# xbowtie2.net
KiCad netlist of a schematic drawn in Altium Designer
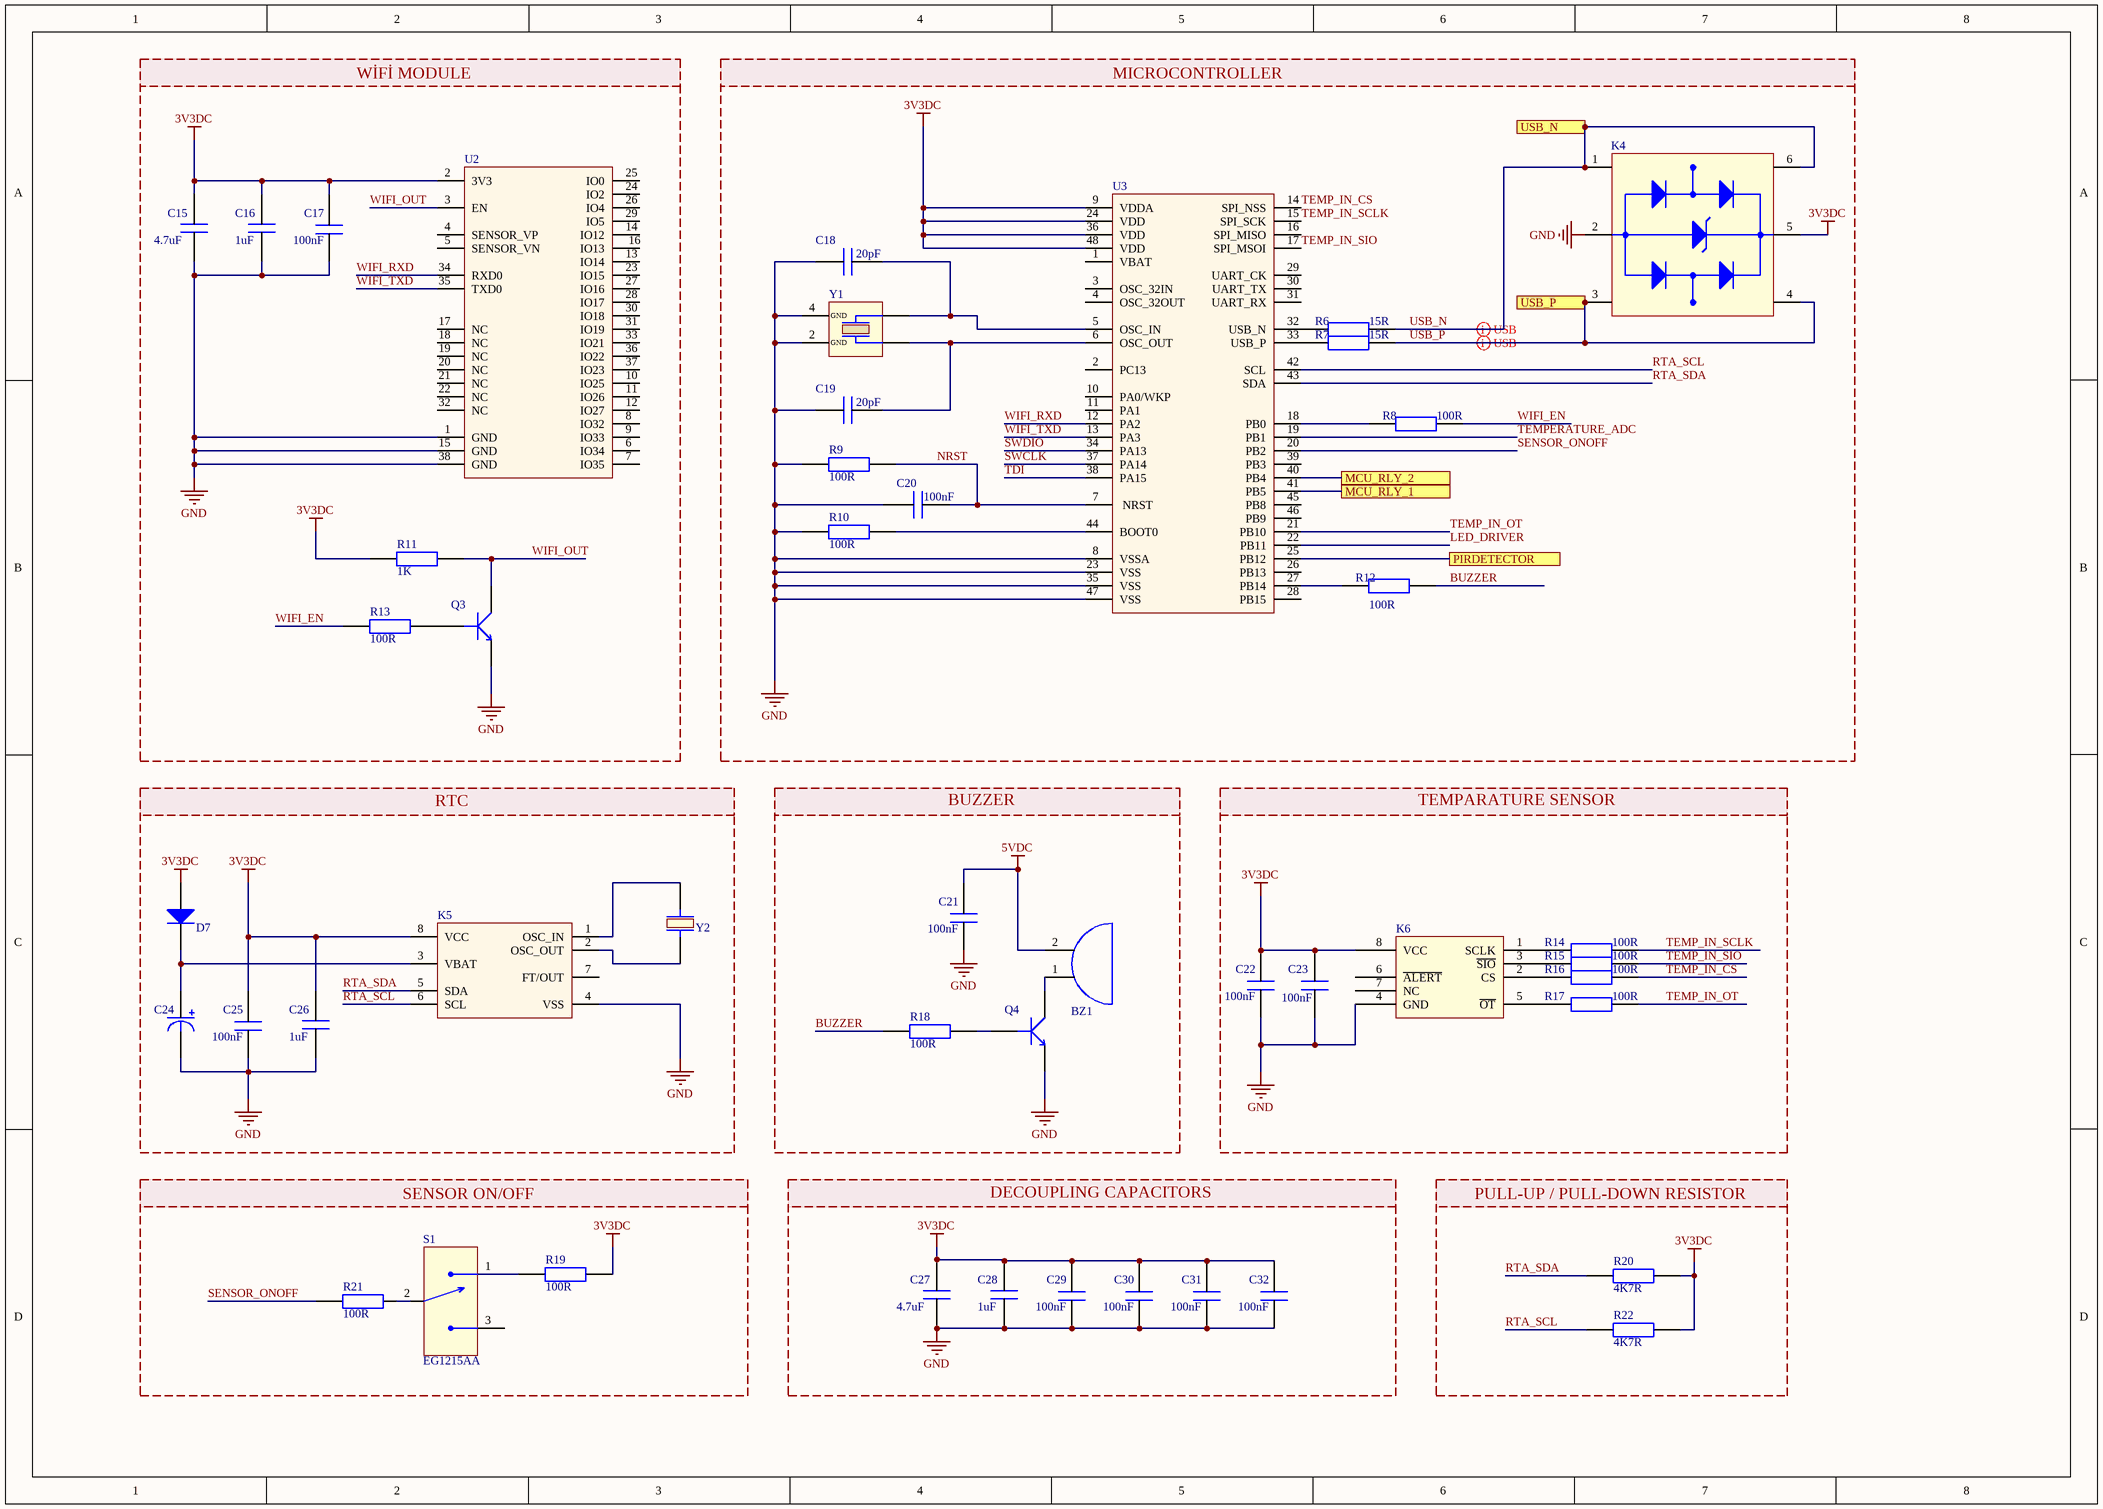
[diagram p0: xbowtie2.SchDoc]

(export (version "E")
  (design (tool "Eeschema 10.0.6"))
  (components
    (comp (ref "BZ1")
      (value "CMI-9605IC-0580T")
      (footprint "CMI-9605IC")
      (description "Audio Buzzer Magnetic 3VDC 7VDC 30mA 5VDC 85dB 2600Hz to 2800Hz Through Hole Pin Box")
      (fields (field (name "MANUFACTURER") "CUI Devices"))
      (libsource (lib "xbowtie") (part "CMI-9605IC-0580T"))
    )
    (comp (ref "C15")
      (value "CAP CER 4.7uF 0805")
      (footprint "CAP_CER 0805")
      (fields
        (field (name "MANUFACTURER") "Samsung")
        (field (name "MANUFACTURER PART NUMBER") "CL21A475KBQNNNE")
        (field (name "TOLERANCE") "10%")
        (field (name "CAPACITANCE") "4.7uF")
      )
      (libsource (lib "xbowtie") (part "CAP CER 4.7uF 0805"))
    )
    (comp (ref "C16")
      (value "1uF")
      (footprint "CAP_CER 0805")
      (description "CAP CER 1uF %10 0805")
      (fields
        (field (name "MANUFACTURER") "Samsung")
        (field (name "MANUFACTURER PART NUMBER") "CL21B105KBFNNNE")
      )
      (libsource (lib "xbowtie") (part "CAP CER 1uF 0805"))
    )
    (comp (ref "C17")
      (value "100nF")
      (footprint "CAP_CER 0805")
      (libsource (lib "xbowtie") (part "CAP CER 100nF 0805"))
    )
    (comp (ref "C18") (value "20pF") (libsource (lib "xbowtie") (part "CAP CER 20 pF 0603")))
    (comp (ref "C19") (value "20pF") (libsource (lib "xbowtie") (part "CAP CER 20 pF 0603")))
    (comp (ref "C20")
      (value "100nF")
      (footprint "CAP_CER 0805")
      (libsource (lib "xbowtie") (part "CAP CER 100nF 0805"))
    )
    (comp (ref "C21")
      (value "100nF")
      (footprint "CAP_CER 0805")
      (libsource (lib "xbowtie") (part "CAP CER 100nF 0805"))
    )
    (comp (ref "C22")
      (value "100nF")
      (footprint "CAP_CER 0805")
      (libsource (lib "xbowtie") (part "CAP CER 100nF 0805"))
    )
    (comp (ref "C23")
      (value "100nF")
      (footprint "CAP_CER 0805")
      (libsource (lib "xbowtie") (part "CAP CER 100nF 0805"))
    )
    (comp (ref "C24")
      (value "ESH477M050AH4AA")
      (footprint "ESH477")
      (description "Cap, 470UF, 50V, Alu Elec, Radial")
      (fields (field (name "MANUFACTURER") "KEMET"))
      (libsource (lib "xbowtie") (part "CAP ALU ELEC 470 uF 50V"))
    )
    (comp (ref "C25")
      (value "100nF")
      (footprint "CAP_CER 0805")
      (libsource (lib "xbowtie") (part "CAP CER 100nF 0805"))
    )
    (comp (ref "C26")
      (value "1uF")
      (footprint "CAP_CER 0805")
      (description "CAP CER 1uF %10 0805")
      (fields
        (field (name "MANUFACTURER") "Samsung")
        (field (name "MANUFACTURER PART NUMBER") "CL21B105KBFNNNE")
      )
      (libsource (lib "xbowtie") (part "CAP CER 1uF 0805"))
    )
    (comp (ref "C27")
      (value "CAP CER 4.7uF 0805")
      (footprint "CAP_CER 0805")
      (fields
        (field (name "MANUFACTURER") "Samsung")
        (field (name "MANUFACTURER PART NUMBER") "CL21A475KBQNNNE")
        (field (name "TOLERANCE") "10%")
        (field (name "CAPACITANCE") "4.7uF")
      )
      (libsource (lib "xbowtie") (part "CAP CER 4.7uF 0805"))
    )
    (comp (ref "C28")
      (value "1uF")
      (footprint "CAP_CER 0805")
      (description "CAP CER 1uF %10 0805")
      (fields
        (field (name "MANUFACTURER") "Samsung")
        (field (name "MANUFACTURER PART NUMBER") "CL21B105KBFNNNE")
      )
      (libsource (lib "xbowtie") (part "CAP CER 1uF 0805"))
    )
    (comp (ref "C29")
      (value "100nF")
      (footprint "CAP_CER 0805")
      (libsource (lib "xbowtie") (part "CAP CER 100nF 0805"))
    )
    (comp (ref "C30")
      (value "100nF")
      (footprint "CAP_CER 0805")
      (libsource (lib "xbowtie") (part "CAP CER 100nF 0805"))
    )
    (comp (ref "C31")
      (value "100nF")
      (footprint "CAP_CER 0805")
      (libsource (lib "xbowtie") (part "CAP CER 100nF 0805"))
    )
    (comp (ref "C32")
      (value "100nF")
      (footprint "CAP_CER 0805")
      (libsource (lib "xbowtie") (part "CAP CER 100nF 0805"))
    )
    (comp (ref "D7")
      (value "1N4148WS")
      (footprint "1N4148WS")
      (description "Diode Ultra Fast Recovery Rectifier 75V 0.15A 2-Pin SOD-323F T/R")
      (fields (field (name "MANUFACTURER") "ON Semiconductor / Fairchild"))
      (libsource (lib "xbowtie") (part "1N4148WS"))
    )
    (comp (ref "K4")
      (value "USBLC6-2SC6")
      (footprint "USBLC6-2SC6")
      (libsource (lib "xbowtie") (part "USBLC6-2SC6"))
    )
    (comp (ref "K5")
      (value "M41T00M6F")
      (footprint "M41T00M6F")
      (description "Real-time Clocks Clock/Calendar I2C, 2-Wire Serial 70uA @ 2V ~ 5.5V SOIC-8_150mil RoHS")
      (fields (field (name "MANUFACTURER") "STMicroelectronics"))
      (libsource (lib "xbowtie") (part "M41T00M6F"))
    )
    (comp (ref "K6")
      (value "MAX6662")
      (footprint "MAKSİMUMA 6662MSA+")
      (description "Temp Sensor Digital Serial (3-Wire, SPI) 8-Pin SOIC N Tube")
      (fields (field (name "MANUFACTURER") "Maxim") (field (name "MANUFACTURER PART NUMBER") "MAX6662MSA+"))
      (libsource (lib "xbowtie") (part "MAX6662"))
    )
    (comp (ref "Q3")
      (value "MMBT3904-7-F")
      (footprint "MMBT3904-7-F")
      (description "Transistor General Purpose BJT NPN 40 Volt 0.2A Automotive 3-Pin SOT-23")
      (fields (field (name "MANUFACTURER") "Diodes Zetex"))
      (libsource (lib "xbowtie") (part "MMBT3904-7-F"))
    )
    (comp (ref "Q4")
      (value "MMBT3904-7-F")
      (footprint "MMBT3904-7-F")
      (description "Transistor General Purpose BJT NPN 40 Volt 0.2A Automotive 3-Pin SOT-23")
      (fields (field (name "MANUFACTURER") "Diodes Zetex"))
      (libsource (lib "xbowtie") (part "MMBT3904-7-F"))
    )
    (comp (ref "R6")
      (value "15R")
      (footprint "RES_0603")
      (libsource (lib "xbowtie") (part "RES 15 OHM 0603"))
    )
    (comp (ref "R7")
      (value "15R")
      (footprint "RES_0603")
      (libsource (lib "xbowtie") (part "RES 15 OHM 0603"))
    )
    (comp (ref "R8")
      (value "100R")
      (footprint "RES_0603")
      (libsource (lib "xbowtie") (part "RES 100 OHM 0603"))
    )
    (comp (ref "R9")
      (value "100R")
      (footprint "RES_0603")
      (libsource (lib "xbowtie") (part "RES 100 OHM 0603"))
    )
    (comp (ref "R10")
      (value "100R")
      (footprint "RES_0603")
      (libsource (lib "xbowtie") (part "RES 100 OHM 0603"))
    )
    (comp (ref "R11")
      (value "1K")
      (footprint "RES_0603")
      (libsource (lib "xbowtie") (part "RES 1K OHM 0603"))
    )
    (comp (ref "R12")
      (value "100R")
      (footprint "RES_0603")
      (libsource (lib "xbowtie") (part "RES 100 OHM 0603"))
    )
    (comp (ref "R13")
      (value "100R")
      (footprint "RES_0603")
      (libsource (lib "xbowtie") (part "RES 100 OHM 0603"))
    )
    (comp (ref "R14")
      (value "100R")
      (footprint "RES_0603")
      (libsource (lib "xbowtie") (part "RES 100 OHM 0603"))
    )
    (comp (ref "R15")
      (value "100R")
      (footprint "RES_0603")
      (libsource (lib "xbowtie") (part "RES 100 OHM 0603"))
    )
    (comp (ref "R16")
      (value "100R")
      (footprint "RES_0603")
      (libsource (lib "xbowtie") (part "RES 100 OHM 0603"))
    )
    (comp (ref "R17")
      (value "100R")
      (footprint "RES_0603")
      (libsource (lib "xbowtie") (part "RES 100 OHM 0603"))
    )
    (comp (ref "R18")
      (value "100R")
      (footprint "RES_0603")
      (libsource (lib "xbowtie") (part "RES 100 OHM 0603"))
    )
    (comp (ref "R19")
      (value "100R")
      (footprint "RES_0603")
      (libsource (lib "xbowtie") (part "RES 100 OHM 0603"))
    )
    (comp (ref "R20")
      (value "4K7R")
      (footprint "RES_0603")
      (libsource (lib "xbowtie") (part "RES 4K7 OHM 0603"))
    )
    (comp (ref "R21")
      (value "100R")
      (footprint "RES_0603")
      (libsource (lib "xbowtie") (part "RES 100 OHM 0603"))
    )
    (comp (ref "R22")
      (value "4K7R")
      (footprint "RES_0603")
      (libsource (lib "xbowtie") (part "RES 4K7 OHM 0603"))
    )
    (comp (ref "S1")
      (value "EG1215AA")
      (footprint "EG1215AA")
      (description "Slide Switch, SPDT, 0.025A, 24V, SMD")
      (fields (field (name "MANUFACTURER") "E-Switch"))
      (libsource (lib "xbowtie") (part "EG1215AA"))
    )
    (comp (ref "U2")
      (value "ESP32-WROOM-32E (4MB)")
      (footprint "ESP32-32E")
      (libsource (lib "xbowtie") (part "ESP32-WROOM-32E (4MB)"))
    )
    (comp (ref "U3")
      (value "STM32F103C6T6A")
      (footprint "STM32")
      (description "MCU 32-bit STM32F ARM Cortex M3 RISC 32KB Flash 2.5V/3.3V 48-Pin LQFP Tray")
      (fields (field (name "MANUFACTURER") "STMicroelectronics"))
      (libsource (lib "xbowtie") (part "STM32F103C6T6A"))
    )
    (comp (ref "Y1")
      (value "CRYSTAL 16MHz")
      (footprint "ECS")
      (libsource (lib "xbowtie") (part "CRYSTAL 16MHz"))
    )
    (comp (ref "Y2")
      (value "CRYSTAL 32.7680KHZ 12.5PF SMD")
      (footprint "ABS05")
      (description "CRYSTAL 32.768kHz ±20ppm Crystal 12.5pF 90 kOhm -40°C ^ 85°C Surface Mount 2-SMD")
      (fields
        (field (name "MANUFACTURER") "Abracon")
        (field (name "MANUFACTURER PART NUMBER") "ABS05-32.768KHZ-T")
      )
      (libsource (lib "xbowtie") (part "CRYSTAL 32768kHz"))
    )
  )
  (nets
    (net (code "1") (name "/BUZZER") (class "Default")
      (node (ref "R12") (pin "2") (pinfunction "2_2") (pintype "passive"))
      (node (ref "R18") (pin "1") (pinfunction "1_1") (pintype "passive"))
    )
    (net (code "2") (name "/LED_DRIVER") (class "Default")
      (node (ref "U3") (pin "22") (pinfunction "PB11_22") (pintype "passive"))
    )
    (net (code "3") (name "/MCU_RLY_1") (class "Default")
      (node (ref "U3") (pin "41") (pinfunction "PB5_41") (pintype "passive"))
    )
    (net (code "4") (name "/MCU_RLY_2") (class "Default")
      (node (ref "U3") (pin "40") (pinfunction "PB4_40") (pintype "passive"))
    )
    (net (code "5") (name "/NRST") (class "Default")
      (node (ref "C20") (pin "1") (pinfunction "1_1") (pintype "passive"))
      (node (ref "R9") (pin "2") (pinfunction "2_2") (pintype "passive"))
      (node (ref "U3") (pin "7") (pinfunction "_NRST_7") (pintype "passive"))
    )
    (net (code "6") (name "/PIRDETECTOR") (class "Default")
      (node (ref "U3") (pin "25") (pinfunction "PB12_25") (pintype "passive"))
    )
    (net (code "7") (name "/RTA_SCL") (class "Default")
      (node (ref "K5") (pin "6") (pinfunction "SCL_6") (pintype "passive"))
      (node (ref "R22") (pin "1") (pinfunction "1_1") (pintype "passive"))
      (node (ref "U3") (pin "42") (pinfunction "SCL_42") (pintype "passive"))
    )
    (net (code "8") (name "/RTA_SDA") (class "Default")
      (node (ref "K5") (pin "5") (pinfunction "SDA_5") (pintype "passive"))
      (node (ref "R20") (pin "1") (pinfunction "1_1") (pintype "passive"))
      (node (ref "U3") (pin "43") (pinfunction "SDA_43") (pintype "passive"))
    )
    (net (code "9") (name "/SENSOR_ONOFF") (class "Default")
      (node (ref "R21") (pin "1") (pinfunction "1_1") (pintype "passive"))
      (node (ref "U3") (pin "20") (pinfunction "PB2_20") (pintype "passive"))
    )
    (net (code "10") (name "/SWCLK") (class "Default")
      (node (ref "U3") (pin "37") (pinfunction "PA14_37") (pintype "passive"))
    )
    (net (code "11") (name "/SWDIO") (class "Default")
      (node (ref "U3") (pin "34") (pinfunction "PA13_34") (pintype "passive"))
    )
    (net (code "12") (name "/TDI") (class "Default")
      (node (ref "U3") (pin "38") (pinfunction "PA15_38") (pintype "passive"))
    )
    (net (code "13") (name "/TEMPERATURE_ADC") (class "Default")
      (node (ref "U3") (pin "19") (pinfunction "PB1_19") (pintype "passive"))
    )
    (net (code "14") (name "/TEMP_IN_CS") (class "Default")
      (node (ref "R16") (pin "2") (pinfunction "2_2") (pintype "passive"))
      (node (ref "U3") (pin "14") (pinfunction "SPI_NSS_14") (pintype "passive"))
    )
    (net (code "15") (name "/TEMP_IN_OT") (class "Default")
      (node (ref "R17") (pin "2") (pinfunction "2_2") (pintype "passive"))
      (node (ref "U3") (pin "21") (pinfunction "PB10_21") (pintype "passive"))
    )
    (net (code "16") (name "/TEMP_IN_SCLK") (class "Default")
      (node (ref "R14") (pin "2") (pinfunction "2_2") (pintype "passive"))
      (node (ref "U3") (pin "15") (pinfunction "SPI_SCK_15") (pintype "passive"))
    )
    (net (code "17") (name "/TEMP_IN_SIO") (class "Default")
      (node (ref "R15") (pin "2") (pinfunction "2_2") (pintype "passive"))
      (node (ref "U3") (pin "17") (pinfunction "SPI_MSOI_17") (pintype "passive"))
    )
    (net (code "18") (name "/USB_N") (class "Default")
      (node (ref "K4") (pin "1") (pinfunction "I/O1_IN_1") (pintype "power_in"))
      (node (ref "K4") (pin "6") (pinfunction "I/O1_OUT_6") (pintype "power_in"))
      (node (ref "R6") (pin "2") (pinfunction "2_2") (pintype "passive"))
    )
    (net (code "19") (name "/USB_P") (class "Default")
      (node (ref "K4") (pin "3") (pinfunction "I/O2_IN_3") (pintype "power_in"))
      (node (ref "K4") (pin "4") (pinfunction "I/O2_OUT_4") (pintype "power_in"))
      (node (ref "R7") (pin "2") (pinfunction "2_2") (pintype "passive"))
    )
    (net (code "20") (name "/WIFI_EN") (class "Default")
      (node (ref "R13") (pin "1") (pinfunction "1_1") (pintype "passive"))
      (node (ref "R8") (pin "2") (pinfunction "2_2") (pintype "passive"))
    )
    (net (code "21") (name "/WIFI_OUT") (class "Default")
      (node (ref "Q3") (pin "C") (pinfunction "C_C") (pintype "passive"))
      (node (ref "R11") (pin "2") (pinfunction "2_2") (pintype "passive"))
      (node (ref "U2") (pin "3") (pinfunction "EN_3") (pintype "passive"))
    )
    (net (code "22") (name "/WIFI_RXD") (class "Default")
      (node (ref "U2") (pin "34") (pinfunction "RXD0_34") (pintype "passive"))
      (node (ref "U3") (pin "12") (pinfunction "PA2_12") (pintype "passive"))
    )
    (net (code "23") (name "/WIFI_TXD") (class "Default")
      (node (ref "U2") (pin "35") (pinfunction "TXD0_35") (pintype "passive"))
      (node (ref "U3") (pin "13") (pinfunction "PA3_13") (pintype "passive"))
    )
    (net (code "24") (name "3V3DC") (class "Default")
      (node (ref "C15") (pin "2") (pinfunction "2_2") (pintype "passive"))
      (node (ref "C16") (pin "2") (pinfunction "2_2") (pintype "passive"))
      (node (ref "C17") (pin "2") (pinfunction "2_2") (pintype "passive"))
      (node (ref "C22") (pin "2") (pinfunction "2_2") (pintype "passive"))
      (node (ref "C23") (pin "2") (pinfunction "2_2") (pintype "passive"))
      (node (ref "C25") (pin "2") (pinfunction "2_2") (pintype "passive"))
      (node (ref "C26") (pin "2") (pinfunction "2_2") (pintype "passive"))
      (node (ref "C27") (pin "2") (pinfunction "2_2") (pintype "passive"))
      (node (ref "C28") (pin "2") (pinfunction "2_2") (pintype "passive"))
      (node (ref "C29") (pin "2") (pinfunction "2_2") (pintype "passive"))
      (node (ref "C30") (pin "2") (pinfunction "2_2") (pintype "passive"))
      (node (ref "C31") (pin "2") (pinfunction "2_2") (pintype "passive"))
      (node (ref "C32") (pin "2") (pinfunction "2_2") (pintype "passive"))
      (node (ref "D7") (pin "2") (pinfunction "2_2") (pintype "passive"))
      (node (ref "K4") (pin "5") (pinfunction "VBUS_5") (pintype "power_in"))
      (node (ref "K5") (pin "8") (pinfunction "VCC_8") (pintype "passive"))
      (node (ref "K6") (pin "8") (pinfunction "VCC_8") (pintype "passive"))
      (node (ref "R11") (pin "1") (pinfunction "1_1") (pintype "passive"))
      (node (ref "R19") (pin "2") (pinfunction "2_2") (pintype "passive"))
      (node (ref "R20") (pin "2") (pinfunction "2_2") (pintype "passive"))
      (node (ref "R22") (pin "2") (pinfunction "2_2") (pintype "passive"))
      (node (ref "U2") (pin "2") (pinfunction "3V3_2") (pintype "passive"))
      (node (ref "U3") (pin "24") (pinfunction "VDD_24") (pintype "passive"))
      (node (ref "U3") (pin "36") (pinfunction "VDD_36") (pintype "passive"))
      (node (ref "U3") (pin "48") (pinfunction "VDD_48") (pintype "passive"))
      (node (ref "U3") (pin "9") (pinfunction "VDDA_9") (pintype "passive"))
    )
    (net (code "25") (name "5VDC") (class "Default")
      (node (ref "BZ1") (pin "2") (pinfunction "2_2") (pintype "passive"))
      (node (ref "C21") (pin "2") (pinfunction "2_2") (pintype "passive"))
    )
    (net (code "26") (name "GND") (class "Default")
      (node (ref "C15") (pin "1") (pinfunction "1_1") (pintype "passive"))
      (node (ref "C16") (pin "1") (pinfunction "1_1") (pintype "passive"))
      (node (ref "C17") (pin "1") (pinfunction "1_1") (pintype "passive"))
      (node (ref "C18") (pin "1") (pinfunction "1_1") (pintype "passive"))
      (node (ref "C19") (pin "1") (pinfunction "1_1") (pintype "passive"))
      (node (ref "C20") (pin "2") (pinfunction "2_2") (pintype "passive"))
      (node (ref "C21") (pin "1") (pinfunction "1_1") (pintype "passive"))
      (node (ref "C22") (pin "1") (pinfunction "1_1") (pintype "passive"))
      (node (ref "C23") (pin "1") (pinfunction "1_1") (pintype "passive"))
      (node (ref "C24") (pin "2") (pinfunction "2_2") (pintype "passive"))
      (node (ref "C25") (pin "1") (pinfunction "1_1") (pintype "passive"))
      (node (ref "C26") (pin "1") (pinfunction "1_1") (pintype "passive"))
      (node (ref "C27") (pin "1") (pinfunction "1_1") (pintype "passive"))
      (node (ref "C28") (pin "1") (pinfunction "1_1") (pintype "passive"))
      (node (ref "C29") (pin "1") (pinfunction "1_1") (pintype "passive"))
      (node (ref "C30") (pin "1") (pinfunction "1_1") (pintype "passive"))
      (node (ref "C31") (pin "1") (pinfunction "1_1") (pintype "passive"))
      (node (ref "C32") (pin "1") (pinfunction "1_1") (pintype "passive"))
      (node (ref "K4") (pin "2") (pinfunction "GND_2") (pintype "power_in"))
      (node (ref "K5") (pin "4") (pinfunction "VSS_4") (pintype "passive"))
      (node (ref "K6") (pin "4") (pinfunction "GND_4") (pintype "passive"))
      (node (ref "Q3") (pin "2") (pinfunction "E_2") (pintype "passive"))
      (node (ref "Q4") (pin "2") (pinfunction "E_2") (pintype "passive"))
      (node (ref "R10") (pin "1") (pinfunction "1_1") (pintype "passive"))
      (node (ref "R9") (pin "1") (pinfunction "1_1") (pintype "passive"))
      (node (ref "U2") (pin "1") (pinfunction "GND_1") (pintype "passive"))
      (node (ref "U2") (pin "15") (pinfunction "GND_15") (pintype "passive"))
      (node (ref "U2") (pin "38") (pinfunction "GND_38") (pintype "passive"))
      (node (ref "U3") (pin "23") (pinfunction "VSS_23") (pintype "passive"))
      (node (ref "U3") (pin "35") (pinfunction "VSS_35") (pintype "passive"))
      (node (ref "U3") (pin "47") (pinfunction "VSS_47") (pintype "passive"))
      (node (ref "U3") (pin "8") (pinfunction "VSSA_8") (pintype "passive"))
      (node (ref "Y1") (pin "2") (pinfunction "GND_2") (pintype "passive"))
      (node (ref "Y1") (pin "4") (pinfunction "GND_4") (pintype "passive"))
    )
    (net (code "27") (name "Net-(BZ1-Pad1)") (class "Default")
      (node (ref "BZ1") (pin "1") (pinfunction "1_1") (pintype "passive"))
      (node (ref "Q4") (pin "C") (pinfunction "C_C") (pintype "passive"))
    )
    (net (code "28") (name "Net-(K5-OSC_IN)") (class "Default")
      (node (ref "K5") (pin "1") (pinfunction "OSC_IN_1") (pintype "passive"))
      (node (ref "Y2") (pin "2") (pinfunction "2_2") (pintype "passive"))
    )
    (net (code "29") (name "Net-(K5-OSC_OUT)") (class "Default")
      (node (ref "K5") (pin "2") (pinfunction "OSC_OUT_2") (pintype "passive"))
      (node (ref "Y2") (pin "1") (pinfunction "1_1") (pintype "passive"))
    )
    (net (code "30") (name "Net-(K5-VBAT)") (class "Default")
      (node (ref "C24") (pin "1") (pinfunction "1_1") (pintype "passive"))
      (node (ref "D7") (pin "1") (pinfunction "1_1") (pintype "passive"))
      (node (ref "K5") (pin "3") (pinfunction "VBAT_3") (pintype "passive"))
    )
    (net (code "31") (name "Net-(K6-CS)") (class "Default")
      (node (ref "K6") (pin "2") (pinfunction "CS_2") (pintype "passive"))
      (node (ref "R16") (pin "1") (pinfunction "1_1") (pintype "passive"))
    )
    (net (code "32") (name "Net-(K6-SCLK)") (class "Default")
      (node (ref "K6") (pin "1") (pinfunction "SCLK_1") (pintype "passive"))
      (node (ref "R14") (pin "1") (pinfunction "1_1") (pintype "passive"))
    )
    (net (code "33") (name "Net-(K6-~{OT})") (class "Default")
      (node (ref "K6") (pin "5") (pinfunction "~{OT}_5") (pintype "passive"))
      (node (ref "R17") (pin "1") (pinfunction "1_1") (pintype "passive"))
    )
    (net (code "34") (name "Net-(K6-~{SIO})") (class "Default")
      (node (ref "K6") (pin "3") (pinfunction "~{SIO}_3") (pintype "passive"))
      (node (ref "R15") (pin "1") (pinfunction "1_1") (pintype "passive"))
    )
    (net (code "35") (name "Net-(Q3-B)") (class "Default")
      (node (ref "Q3") (pin "1") (pinfunction "B_1") (pintype "passive"))
      (node (ref "R13") (pin "2") (pinfunction "2_2") (pintype "passive"))
    )
    (net (code "36") (name "Net-(Q4-B)") (class "Default")
      (node (ref "Q4") (pin "1") (pinfunction "B_1") (pintype "passive"))
      (node (ref "R18") (pin "2") (pinfunction "2_2") (pintype "passive"))
    )
    (net (code "37") (name "Net-(R19-Pad1)") (class "Default")
      (node (ref "R19") (pin "1") (pinfunction "1_1") (pintype "passive"))
      (node (ref "S1") (pin "1") (pinfunction "1_1") (pintype "passive"))
    )
    (net (code "38") (name "Net-(R21-Pad2)") (class "Default")
      (node (ref "R21") (pin "2") (pinfunction "2_2") (pintype "passive"))
      (node (ref "S1") (pin "2") (pinfunction "2_2") (pintype "passive"))
    )
    (net (code "39") (name "Net-(U3-BOOT0)") (class "Default")
      (node (ref "R10") (pin "2") (pinfunction "2_2") (pintype "passive"))
      (node (ref "U3") (pin "44") (pinfunction "BOOT0_44") (pintype "passive"))
    )
    (net (code "40") (name "Net-(U3-OSC_IN)") (class "Default")
      (node (ref "C18") (pin "2") (pinfunction "2_2") (pintype "passive"))
      (node (ref "U3") (pin "5") (pinfunction "OSC_IN_5") (pintype "passive"))
      (node (ref "Y1") (pin "3") (pinfunction "3_3") (pintype "passive"))
    )
    (net (code "41") (name "Net-(U3-OSC_OUT)") (class "Default")
      (node (ref "C19") (pin "2") (pinfunction "2_2") (pintype "passive"))
      (node (ref "U3") (pin "6") (pinfunction "OSC_OUT_6") (pintype "passive"))
      (node (ref "Y1") (pin "1") (pinfunction "1_1") (pintype "passive"))
    )
    (net (code "42") (name "Net-(U3-PB0)") (class "Default")
      (node (ref "R8") (pin "1") (pinfunction "1_1") (pintype "passive"))
      (node (ref "U3") (pin "18") (pinfunction "PB0_18") (pintype "passive"))
    )
    (net (code "43") (name "Net-(U3-PB14)") (class "Default")
      (node (ref "R12") (pin "1") (pinfunction "1_1") (pintype "passive"))
      (node (ref "U3") (pin "27") (pinfunction "PB14_27") (pintype "passive"))
    )
    (net (code "44") (name "Net-(U3-USB_N)") (class "Default")
      (node (ref "R6") (pin "1") (pinfunction "1_1") (pintype "passive"))
      (node (ref "U3") (pin "32") (pinfunction "USB_N_32") (pintype "passive"))
    )
    (net (code "45") (name "Net-(U3-USB_P)") (class "Default")
      (node (ref "R7") (pin "1") (pinfunction "1_1") (pintype "passive"))
      (node (ref "U3") (pin "33") (pinfunction "USB_P_33") (pintype "passive"))
    )
    (net (code "46") (name "unconnected-(K5-FT{slash}OUT-Pad7)") (class "Default")
      (node (ref "K5") (pin "7") (pinfunction "FT/OUT_7") (pintype "passive"))
    )
    (net (code "47") (name "unconnected-(K6-NC-Pad7)") (class "Default")
      (node (ref "K6") (pin "7") (pinfunction "NC_7") (pintype "passive"))
    )
    (net (code "48") (name "unconnected-(K6-~{ALERT}-Pad6)") (class "Default")
      (node (ref "K6") (pin "6") (pinfunction "~{ALERT}_6") (pintype "passive"))
    )
    (net (code "49") (name "unconnected-(S1-Pad3)") (class "Default")
      (node (ref "S1") (pin "3") (pinfunction "3_3") (pintype "passive"))
    )
    (net (code "50") (name "unconnected-(U2-IO0-Pad25)") (class "Default")
      (node (ref "U2") (pin "25") (pinfunction "IO0_25") (pintype "passive"))
    )
    (net (code "51") (name "unconnected-(U2-IO2-Pad24)") (class "Default")
      (node (ref "U2") (pin "24") (pinfunction "IO2_24") (pintype "passive"))
    )
    (net (code "52") (name "unconnected-(U2-IO4-Pad26)") (class "Default")
      (node (ref "U2") (pin "26") (pinfunction "IO4_26") (pintype "passive"))
    )
    (net (code "53") (name "unconnected-(U2-IO5-Pad29)") (class "Default")
      (node (ref "U2") (pin "29") (pinfunction "IO5_29") (pintype "passive"))
    )
    (net (code "54") (name "unconnected-(U2-IO12-Pad14)") (class "Default")
      (node (ref "U2") (pin "14") (pinfunction "IO12_14") (pintype "passive"))
    )
    (net (code "55") (name "unconnected-(U2-IO13-Pad16)") (class "Default")
      (node (ref "U2") (pin "16") (pinfunction "IO13_16") (pintype "passive"))
    )
    (net (code "56") (name "unconnected-(U2-IO14-Pad13)") (class "Default")
      (node (ref "U2") (pin "13") (pinfunction "IO14_13") (pintype "passive"))
    )
    (net (code "57") (name "unconnected-(U2-IO15-Pad23)") (class "Default")
      (node (ref "U2") (pin "23") (pinfunction "IO15_23") (pintype "passive"))
    )
    (net (code "58") (name "unconnected-(U2-IO16-Pad27)") (class "Default")
      (node (ref "U2") (pin "27") (pinfunction "IO16_27") (pintype "passive"))
    )
    (net (code "59") (name "unconnected-(U2-IO17-Pad28)") (class "Default")
      (node (ref "U2") (pin "28") (pinfunction "IO17_28") (pintype "passive"))
    )
    (net (code "60") (name "unconnected-(U2-IO18-Pad30)") (class "Default")
      (node (ref "U2") (pin "30") (pinfunction "IO18_30") (pintype "passive"))
    )
    (net (code "61") (name "unconnected-(U2-IO19-Pad31)") (class "Default")
      (node (ref "U2") (pin "31") (pinfunction "IO19_31") (pintype "passive"))
    )
    (net (code "62") (name "unconnected-(U2-IO21-Pad33)") (class "Default")
      (node (ref "U2") (pin "33") (pinfunction "IO21_33") (pintype "passive"))
    )
    (net (code "63") (name "unconnected-(U2-IO22-Pad36)") (class "Default")
      (node (ref "U2") (pin "36") (pinfunction "IO22_36") (pintype "passive"))
    )
    (net (code "64") (name "unconnected-(U2-IO23-Pad37)") (class "Default")
      (node (ref "U2") (pin "37") (pinfunction "IO23_37") (pintype "passive"))
    )
    (net (code "65") (name "unconnected-(U2-IO25-Pad10)") (class "Default")
      (node (ref "U2") (pin "10") (pinfunction "IO25_10") (pintype "passive"))
    )
    (net (code "66") (name "unconnected-(U2-IO26-Pad11)") (class "Default")
      (node (ref "U2") (pin "11") (pinfunction "IO26_11") (pintype "passive"))
    )
    (net (code "67") (name "unconnected-(U2-IO27-Pad12)") (class "Default")
      (node (ref "U2") (pin "12") (pinfunction "IO27_12") (pintype "passive"))
    )
    (net (code "68") (name "unconnected-(U2-IO32-Pad8)") (class "Default")
      (node (ref "U2") (pin "8") (pinfunction "IO32_8") (pintype "passive"))
    )
    (net (code "69") (name "unconnected-(U2-IO33-Pad9)") (class "Default")
      (node (ref "U2") (pin "9") (pinfunction "IO33_9") (pintype "passive"))
    )
    (net (code "70") (name "unconnected-(U2-IO34-Pad6)") (class "Default")
      (node (ref "U2") (pin "6") (pinfunction "IO34_6") (pintype "passive"))
    )
    (net (code "71") (name "unconnected-(U2-IO35-Pad7)") (class "Default")
      (node (ref "U2") (pin "7") (pinfunction "IO35_7") (pintype "passive"))
    )
    (net (code "72") (name "unconnected-(U2-NC-Pad17)") (class "Default")
      (node (ref "U2") (pin "17") (pinfunction "NC_17") (pintype "passive"))
    )
    (net (code "73") (name "unconnected-(U2-NC-Pad18)") (class "Default")
      (node (ref "U2") (pin "18") (pinfunction "NC_18") (pintype "passive"))
    )
    (net (code "74") (name "unconnected-(U2-NC-Pad19)") (class "Default")
      (node (ref "U2") (pin "19") (pinfunction "NC_19") (pintype "passive"))
    )
    (net (code "75") (name "unconnected-(U2-NC-Pad20)") (class "Default")
      (node (ref "U2") (pin "20") (pinfunction "NC_20") (pintype "passive"))
    )
    (net (code "76") (name "unconnected-(U2-NC-Pad21)") (class "Default")
      (node (ref "U2") (pin "21") (pinfunction "NC_21") (pintype "passive"))
    )
    (net (code "77") (name "unconnected-(U2-NC-Pad22)") (class "Default")
      (node (ref "U2") (pin "22") (pinfunction "NC_22") (pintype "passive"))
    )
    (net (code "78") (name "unconnected-(U2-NC-Pad32)") (class "Default")
      (node (ref "U2") (pin "32") (pinfunction "NC_32") (pintype "passive"))
    )
    (net (code "79") (name "unconnected-(U2-SENSOR_VN-Pad5)") (class "Default")
      (node (ref "U2") (pin "5") (pinfunction "SENSOR_VN_5") (pintype "passive"))
    )
    (net (code "80") (name "unconnected-(U2-SENSOR_VP-Pad4)") (class "Default")
      (node (ref "U2") (pin "4") (pinfunction "SENSOR_VP_4") (pintype "passive"))
    )
    (net (code "81") (name "unconnected-(U3-OSC_32IN-Pad3)") (class "Default")
      (node (ref "U3") (pin "3") (pinfunction "OSC_32IN_3") (pintype "passive"))
    )
    (net (code "82") (name "unconnected-(U3-OSC_32OUT-Pad4)") (class "Default")
      (node (ref "U3") (pin "4") (pinfunction "OSC_32OUT_4") (pintype "passive"))
    )
    (net (code "83") (name "unconnected-(U3-PA0{slash}WKP-Pad10)") (class "Default")
      (node (ref "U3") (pin "10") (pinfunction "PA0/WKP_10") (pintype "passive"))
    )
    (net (code "84") (name "unconnected-(U3-PA1-Pad11)") (class "Default")
      (node (ref "U3") (pin "11") (pinfunction "PA1_11") (pintype "passive"))
    )
    (net (code "85") (name "unconnected-(U3-PB3-Pad39)") (class "Default")
      (node (ref "U3") (pin "39") (pinfunction "PB3_39") (pintype "passive"))
    )
    (net (code "86") (name "unconnected-(U3-PB8-Pad45)") (class "Default")
      (node (ref "U3") (pin "45") (pinfunction "PB8_45") (pintype "passive"))
    )
    (net (code "87") (name "unconnected-(U3-PB9-Pad46)") (class "Default")
      (node (ref "U3") (pin "46") (pinfunction "PB9_46") (pintype "passive"))
    )
    (net (code "88") (name "unconnected-(U3-PB13-Pad26)") (class "Default")
      (node (ref "U3") (pin "26") (pinfunction "PB13_26") (pintype "passive"))
    )
    (net (code "89") (name "unconnected-(U3-PB15-Pad28)") (class "Default")
      (node (ref "U3") (pin "28") (pinfunction "PB15_28") (pintype "passive"))
    )
    (net (code "90") (name "unconnected-(U3-PC13-Pad2)") (class "Default")
      (node (ref "U3") (pin "2") (pinfunction "PC13_2") (pintype "passive"))
    )
    (net (code "91") (name "unconnected-(U3-SPI_MISO-Pad16)") (class "Default")
      (node (ref "U3") (pin "16") (pinfunction "SPI_MISO_16") (pintype "passive"))
    )
    (net (code "92") (name "unconnected-(U3-UART_CK-Pad29)") (class "Default")
      (node (ref "U3") (pin "29") (pinfunction "UART_CK_29") (pintype "passive"))
    )
    (net (code "93") (name "unconnected-(U3-UART_RX-Pad31)") (class "Default")
      (node (ref "U3") (pin "31") (pinfunction "UART_RX_31") (pintype "passive"))
    )
    (net (code "94") (name "unconnected-(U3-UART_TX-Pad30)") (class "Default")
      (node (ref "U3") (pin "30") (pinfunction "UART_TX_30") (pintype "passive"))
    )
    (net (code "95") (name "unconnected-(U3-VBAT-Pad1)") (class "Default")
      (node (ref "U3") (pin "1") (pinfunction "VBAT_1") (pintype "passive"))
    )
  )
)
